# sheet_reg.net
KiCad netlist of a schematic drawn in Altium Designer
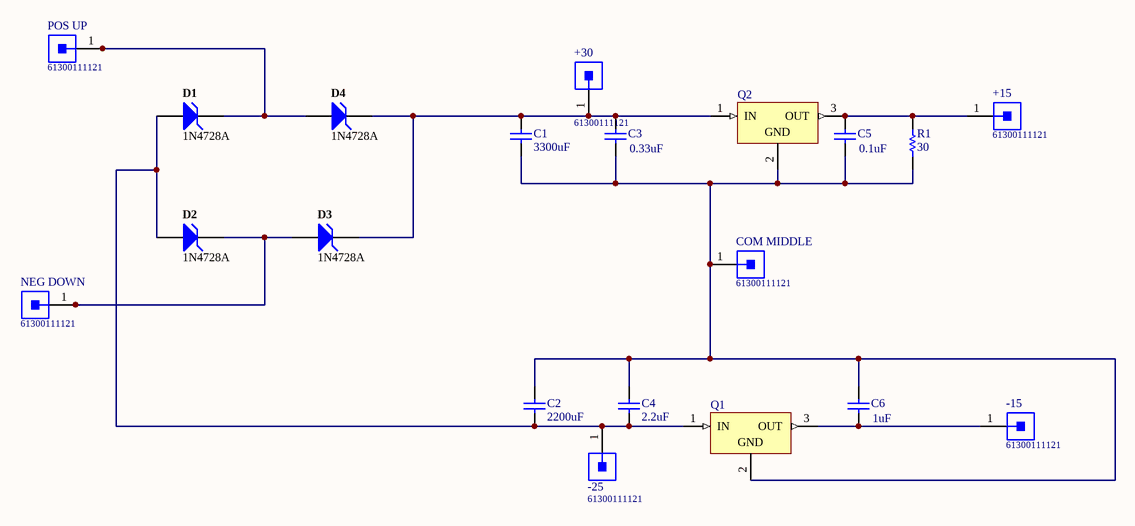
[diagram p0: sheet_reg.SchDoc]

(export (version "E")
  (design (tool "Eeschema 10.0.6"))
  (components
    (comp (ref "+15")
      (value "61300111121")
      (footprint "61300111121")
      (description "THT Vertical Pin Header WR-PHD, Pitch 2.54 mm, Single Row, 1 pins")
      (fields (field (name "MANUFACTURER") "Wurth Elektronik") (field (name "PUBLISHER") "WurthElektronik"))
      (libsource (lib "Altium Content Vault") (part "WE-CN-1P-M-R1"))
    )
    (comp (ref "+30")
      (value "61300111121")
      (footprint "61300111121")
      (description "THT Vertical Pin Header WR-PHD, Pitch 2.54 mm, Single Row, 1 pins")
      (fields (field (name "MANUFACTURER") "Wurth Elektronik") (field (name "PUBLISHER") "WurthElektronik"))
      (libsource (lib "") (part "WE-CN-1P-M-R1_1"))
    )
    (comp (ref "-15")
      (value "61300111121")
      (footprint "61300111121")
      (description "THT Vertical Pin Header WR-PHD, Pitch 2.54 mm, Single Row, 1 pins")
      (fields (field (name "MANUFACTURER") "Wurth Elektronik") (field (name "PUBLISHER") "WurthElektronik"))
      (libsource (lib "Altium Content Vault") (part "WE-CN-1P-M-R1"))
    )
    (comp (ref "-25")
      (value "61300111121")
      (footprint "61300111121")
      (description "THT Vertical Pin Header WR-PHD, Pitch 2.54 mm, Single Row, 1 pins")
      (fields (field (name "MANUFACTURER") "Wurth Elektronik") (field (name "PUBLISHER") "WurthElektronik"))
      (libsource (lib "") (part "WE-CN-1P-M-R1_3"))
    )
    (comp (ref "C1")
      (value "3300uF")
      (footprint "KEMT-C315-THT-2")
      (description "Capacitor, Ceramic, 0.01 uF, +/- 10%, 100 V, X7R, -55 to 125 degC, 2-Pin THD, RoHS, Bulk")
      (libsource (lib "Altium Content Vault") (part "CAP-NP-2"))
    )
    (comp (ref "C2")
      (value "2200uF")
      (footprint "KEMT-C315-THT-2")
      (description "Capacitor, Ceramic, 0.01 uF, +/- 10%, 100 V, X7R, -55 to 125 degC, 2-Pin THD, RoHS, Bulk")
      (libsource (lib "Altium Content Vault") (part "CAP-NP-2"))
    )
    (comp (ref "C3")
      (value "0.33uF")
      (footprint "KEMT-C315-THT-2")
      (description "Capacitor, Ceramic, 0.01 uF, +/- 10%, 100 V, X7R, -55 to 125 degC, 2-Pin THD, RoHS, Bulk")
      (libsource (lib "Altium Content Vault") (part "CAP-NP-2"))
    )
    (comp (ref "C4")
      (value "2.2uF")
      (footprint "KEMT-C315-THT-2")
      (description "Capacitor, Ceramic, 0.01 uF, +/- 10%, 100 V, X7R, -55 to 125 degC, 2-Pin THD, RoHS, Bulk")
      (libsource (lib "Altium Content Vault") (part "CAP-NP-2"))
    )
    (comp (ref "C5")
      (value "0.1uF")
      (footprint "KEMT-C315-THT-2")
      (description "Capacitor, Ceramic, 0.01 uF, +/- 10%, 100 V, X7R, -55 to 125 degC, 2-Pin THD, RoHS, Bulk")
      (libsource (lib "Altium Content Vault") (part "CAP-NP-2"))
    )
    (comp (ref "C6")
      (value "1uF")
      (footprint "KEMT-C315-THT-2")
      (description "Capacitor, Ceramic, 0.01 uF, +/- 10%, 100 V, X7R, -55 to 125 degC, 2-Pin THD, RoHS, Bulk")
      (libsource (lib "Altium Content Vault") (part "CAP-NP-2"))
    )
    (comp (ref "COM MIDDLE")
      (value "61300111121")
      (footprint "61300111121")
      (description "THT Vertical Pin Header WR-PHD, Pitch 2.54 mm, Single Row, 1 pins")
      (fields (field (name "MANUFACTURER") "Wurth Elektronik") (field (name "PUBLISHER") "WurthElektronik"))
      (libsource (lib "Altium Content Vault") (part "WE-CN-1P-M-R1"))
    )
    (comp (ref "D1")
      (value "1N4728A")
      (footprint "FAIR-DO-41-2_V")
      (description "Zener Diode, 3.3V, 1W, 5%, -65 to 200 degC, 2-Pin DO-41, Body 2.72 x 5.2 mm, RoHS")
      (fields (field (name "MANUFACTURER") "Fairchild Semiconductor") (field (name "TOLERANCE") "5%"))
      (libsource (lib "Altium Content Vault") (part "FAIR-DZEN-A1K2-2"))
    )
    (comp (ref "D2")
      (value "1N4728A")
      (footprint "FAIR-DO-41-2_V")
      (description "Zener Diode, 3.3V, 1W, 5%, -65 to 200 degC, 2-Pin DO-41, Body 2.72 x 5.2 mm, RoHS")
      (fields (field (name "MANUFACTURER") "Fairchild Semiconductor") (field (name "TOLERANCE") "5%"))
      (libsource (lib "Altium Content Vault") (part "FAIR-DZEN-A1K2-2"))
    )
    (comp (ref "D3")
      (value "1N4728A")
      (footprint "FAIR-DO-41-2_V")
      (description "Zener Diode, 3.3V, 1W, 5%, -65 to 200 degC, 2-Pin DO-41, Body 2.72 x 5.2 mm, RoHS")
      (fields (field (name "MANUFACTURER") "Fairchild Semiconductor") (field (name "TOLERANCE") "5%"))
      (libsource (lib "Altium Content Vault") (part "FAIR-DZEN-A1K2-2"))
    )
    (comp (ref "D4")
      (value "1N4728A")
      (footprint "FAIR-DO-41-2_V")
      (description "Zener Diode, 3.3V, 1W, 5%, -65 to 200 degC, 2-Pin DO-41, Body 2.72 x 5.2 mm, RoHS")
      (fields (field (name "MANUFACTURER") "Fairchild Semiconductor") (field (name "TOLERANCE") "5%"))
      (libsource (lib "Altium Content Vault") (part "FAIR-DZEN-A1K2-2"))
    )
    (comp (ref "NEG DOWN")
      (value "61300111121")
      (footprint "61300111121")
      (description "THT Vertical Pin Header WR-PHD, Pitch 2.54 mm, Single Row, 1 pins")
      (fields (field (name "MANUFACTURER") "Wurth Elektronik") (field (name "PUBLISHER") "WurthElektronik"))
      (libsource (lib "") (part "WE-CN-1P-M-R1_2"))
    )
    (comp (ref "POS UP")
      (value "61300111121")
      (footprint "61300111121")
      (description "THT Vertical Pin Header WR-PHD, Pitch 2.54 mm, Single Row, 1 pins")
      (fields (field (name "MANUFACTURER") "Wurth Elektronik") (field (name "PUBLISHER") "WurthElektronik"))
      (libsource (lib "") (part "WE-CN-1P-M-R1_2"))
    )
    (comp (ref "Q1")
      (value "~")
      (footprint "FAIR-TO-220-3")
      (description "Positive Voltage Regulator, 5 V, 1 A, -40 to 125 degC, 3-Pin TO-220, RoHS, Tube")
      (fields (field (name "MANUFACTURER") "FairchildSemiconductor"))
      (libsource (lib "Altium Content Vault") (part "FAIR-LM7805CT-TO220-3"))
    )
    (comp (ref "Q2")
      (value "~")
      (footprint "FAIR-TO-220-3")
      (description "Positive Voltage Regulator, 5 V, 1 A, -40 to 125 degC, 3-Pin TO-220, RoHS, Tube")
      (fields (field (name "MANUFACTURER") "FairchildSemiconductor"))
      (libsource (lib "Altium Content Vault") (part "FAIR-LM7805CT-TO220-3"))
    )
    (comp (ref "R1")
      (value "30")
      (footprint "RESA60-630X240")
      (description "Axial Resistor, 1 KOhm, +/- 1%, 250 mW, -55 to 155 degC, 2-Pin THD, RoHS, Bulk")
      (fields (field (name "TOLERANCE") "1%"))
      (libsource (lib "Altium Content Vault") (part "RES-2"))
    )
  )
  (nets
    (net (code "1") (name "Net-(D1-A)") (class "Default")
      (node (ref "-25") (pin "1") (pinfunction "1_1") (pintype "passive"))
      (node (ref "C2") (pin "1") (pinfunction "1_1") (pintype "passive"))
      (node (ref "C4") (pin "1") (pinfunction "1_1") (pintype "passive"))
      (node (ref "D1") (pin "1") (pinfunction "A_1") (pintype "passive"))
      (node (ref "D2") (pin "1") (pinfunction "A_1") (pintype "passive"))
      (node (ref "Q1") (pin "1") (pinfunction "IN_1") (pintype "input"))
    )
    (net (code "2") (name "Net-(D1-K)") (class "Default")
      (node (ref "D1") (pin "2") (pinfunction "K_2") (pintype "passive"))
      (node (ref "D4") (pin "1") (pinfunction "A_1") (pintype "passive"))
      (node (ref "POS UP") (pin "1") (pinfunction "1_1") (pintype "passive"))
    )
    (net (code "3") (name "Net-(D2-K)") (class "Default")
      (node (ref "D2") (pin "2") (pinfunction "K_2") (pintype "passive"))
      (node (ref "D3") (pin "1") (pinfunction "A_1") (pintype "passive"))
      (node (ref "NEG DOWN") (pin "1") (pinfunction "1_1") (pintype "passive"))
    )
    (net (code "4") (name "Net-(D3-K)") (class "Default")
      (node (ref "+30") (pin "1") (pinfunction "1_1") (pintype "passive"))
      (node (ref "C1") (pin "2") (pinfunction "2_2") (pintype "passive"))
      (node (ref "C3") (pin "2") (pinfunction "2_2") (pintype "passive"))
      (node (ref "D3") (pin "2") (pinfunction "K_2") (pintype "passive"))
      (node (ref "D4") (pin "2") (pinfunction "K_2") (pintype "passive"))
      (node (ref "Q2") (pin "1") (pinfunction "IN_1") (pintype "input"))
    )
    (net (code "5") (name "Net-(Q1-GND)") (class "Default")
      (node (ref "C1") (pin "1") (pinfunction "1_1") (pintype "passive"))
      (node (ref "C2") (pin "2") (pinfunction "2_2") (pintype "passive"))
      (node (ref "C3") (pin "1") (pinfunction "1_1") (pintype "passive"))
      (node (ref "C4") (pin "2") (pinfunction "2_2") (pintype "passive"))
      (node (ref "C5") (pin "1") (pinfunction "1_1") (pintype "passive"))
      (node (ref "C6") (pin "2") (pinfunction "2_2") (pintype "passive"))
      (node (ref "COM MIDDLE") (pin "1") (pinfunction "1_1") (pintype "passive"))
      (node (ref "Q1") (pin "2") (pinfunction "GND_2") (pintype "power_in"))
      (node (ref "Q2") (pin "2") (pinfunction "GND_2") (pintype "power_in"))
      (node (ref "R1") (pin "2") (pinfunction "2_2") (pintype "passive"))
    )
    (net (code "6") (name "Net-(Q1-OUT)") (class "Default")
      (node (ref "-15") (pin "1") (pinfunction "1_1") (pintype "passive"))
      (node (ref "C6") (pin "1") (pinfunction "1_1") (pintype "passive"))
      (node (ref "Q1") (pin "3") (pinfunction "OUT_3") (pintype "output"))
    )
    (net (code "7") (name "Net-(Q2-OUT)") (class "Default")
      (node (ref "+15") (pin "1") (pinfunction "1_1") (pintype "passive"))
      (node (ref "C5") (pin "2") (pinfunction "2_2") (pintype "passive"))
      (node (ref "Q2") (pin "3") (pinfunction "OUT_3") (pintype "output"))
      (node (ref "R1") (pin "1") (pinfunction "1_1") (pintype "passive"))
    )
  )
)
